# ccs811_v_1_0.net
KiCad netlist of a schematic drawn in EAGLE
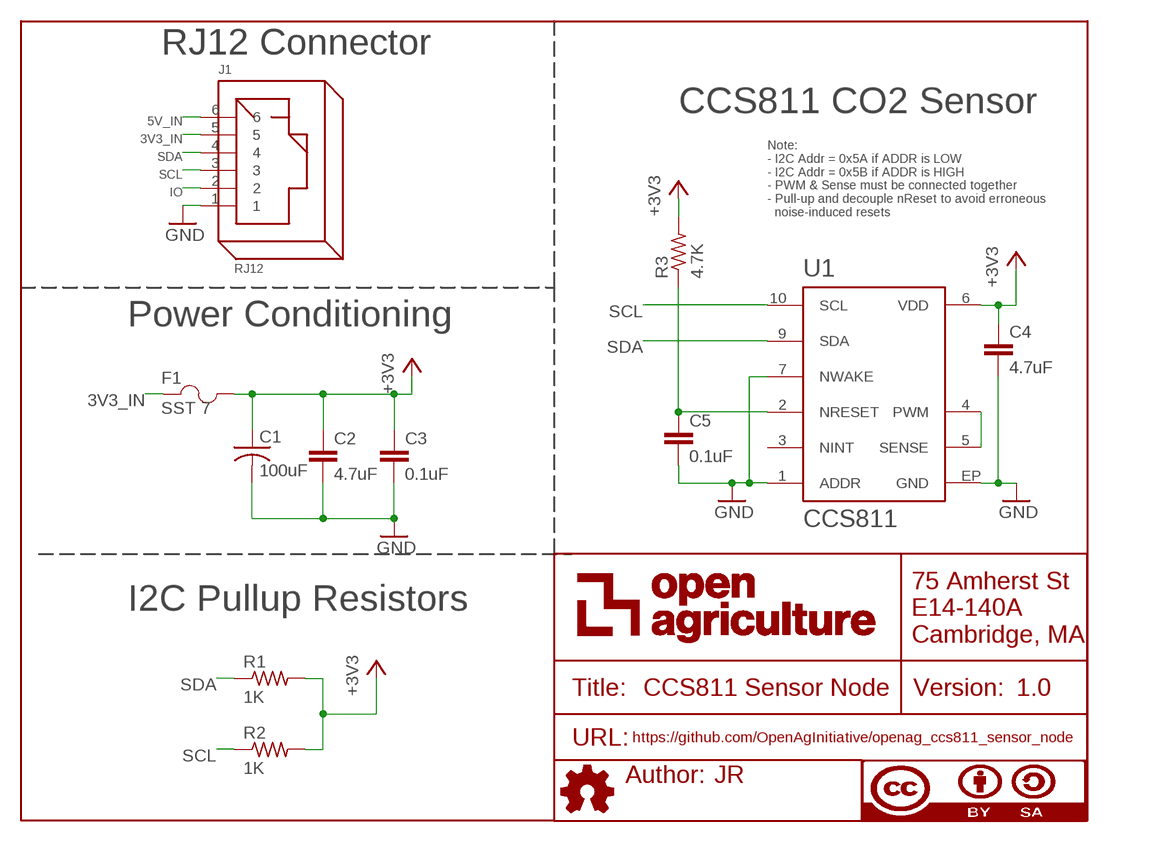
[diagram p0: schematic, sheet 1]

(export (version "E")
  (design (tool "Eeschema 10.0.6"))
  (components
    (comp (ref "C1")
      (value "100uF")
      (footprint "eagle-import:EEE-1HA101UP")
      (libsource (lib "eagle-import") (part "100UF-EEE-1HA101UP"))
    )
    (comp (ref "C2")
      (value "4.7uF")
      (footprint "eagle-import:C0805")
      (libsource (lib "eagle-import") (part "4.7UF-CL21A475KBQNNNE"))
    )
    (comp (ref "C3")
      (value "0.1uF")
      (footprint "eagle-import:C0603")
      (libsource (lib "eagle-import") (part "0.1UF-C0603C104K5RACTU"))
    )
    (comp (ref "C4")
      (value "4.7uF")
      (footprint "eagle-import:C0805")
      (libsource (lib "eagle-import") (part "4.7UF-CL21A475KBQNNNE"))
    )
    (comp (ref "C5")
      (value "0.1uF")
      (footprint "eagle-import:C0603")
      (libsource (lib "eagle-import") (part "0.1UF-C0603C104K5RACTU"))
    )
    (comp (ref "F1")
      (value "SST 7")
      (footprint "eagle-import:SS")
      (libsource (lib "eagle-import") (part "SST_7"))
    )
    (comp (ref "FRAME1")
      (value "DOCFIELD")
      (footprint "eagle-import:DOCFIELD")
      (description "CCS811 CO2 Sensor Node")
      (fields
        (field (name "AUTHOR") "JR")
        (field (name "TITLE") "CCS811 Sensor Node")
        (field (name "URL") "https://github.com/OpenAgInitiative/openag_ccs811_sensor_node")
      )
      (libsource (lib "eagle-import") (part "DOCFIELD"))
    )
    (comp (ref "J1")
      (value "RJ12")
      (footprint "eagle-import:RJ12")
      (libsource (lib "eagle-import") (part "A-2004-1-4-LP-N-R"))
    )
    (comp (ref "R1")
      (value "1K")
      (footprint "eagle-import:RC0603N")
      (libsource (lib "eagle-import") (part "1K-ERJ-PB3D1001V"))
    )
    (comp (ref "R2")
      (value "1K")
      (footprint "eagle-import:RC0603N")
      (libsource (lib "eagle-import") (part "1K-ERJ-PB3D1001V"))
    )
    (comp (ref "R3")
      (value "4.7K")
      (footprint "eagle-import:R1206")
      (libsource (lib "eagle-import") (part "4.7K-RC1206JR-074K7L"))
    )
    (comp (ref "U1")
      (value "CCS811")
      (footprint "eagle-import:CCS811")
      (libsource (lib "eagle-import") (part "CCS811"))
    )
  )
  (nets
    (net (code "1") (name "+3V3") (class "Default")
      (node (ref "C1") (pin "+") (pinfunction "1(+)_+") (pintype "passive"))
      (node (ref "C2") (pin "1") (pinfunction "1_1") (pintype "passive"))
      (node (ref "C3") (pin "1") (pinfunction "1_1") (pintype "passive"))
      (node (ref "C4") (pin "1") (pinfunction "1_1") (pintype "passive"))
      (node (ref "F1") (pin "2") (pinfunction "2_2") (pintype "passive"))
      (node (ref "R1") (pin "2") (pinfunction "2_2") (pintype "passive"))
      (node (ref "R2") (pin "2") (pinfunction "2_2") (pintype "passive"))
      (node (ref "R3") (pin "2") (pinfunction "2_2") (pintype "passive"))
      (node (ref "U1") (pin "6") (pinfunction "VDD_6") (pintype "power_in"))
    )
    (net (code "2") (name "3V3_IN") (class "Default")
      (node (ref "F1") (pin "1") (pinfunction "1_1") (pintype "passive"))
      (node (ref "J1") (pin "5") (pinfunction "5_5") (pintype "bidirectional"))
    )
    (net (code "3") (name "5V_IN") (class "Default")
      (node (ref "J1") (pin "6") (pinfunction "6_6") (pintype "bidirectional"))
    )
    (net (code "4") (name "GND") (class "Default")
      (node (ref "C1") (pin "-") (pinfunction "2(-)_-") (pintype "passive"))
      (node (ref "C2") (pin "2") (pinfunction "2_2") (pintype "passive"))
      (node (ref "C3") (pin "2") (pinfunction "2_2") (pintype "passive"))
      (node (ref "C4") (pin "2") (pinfunction "2_2") (pintype "passive"))
      (node (ref "C5") (pin "2") (pinfunction "2_2") (pintype "passive"))
      (node (ref "J1") (pin "1") (pinfunction "1_1") (pintype "bidirectional"))
      (node (ref "U1") (pin "1") (pinfunction "ADDR_1") (pintype "bidirectional"))
      (node (ref "U1") (pin "7") (pinfunction "NWAKE_7") (pintype "bidirectional"))
      (node (ref "U1") (pin "EP") (pinfunction "GND_EP") (pintype "power_in"))
    )
    (net (code "5") (name "IO") (class "Default")
      (node (ref "J1") (pin "2") (pinfunction "2_2") (pintype "bidirectional"))
    )
    (net (code "6") (name "Net-(U1-NRESET)") (class "Default")
      (node (ref "C5") (pin "1") (pinfunction "1_1") (pintype "passive"))
      (node (ref "R3") (pin "1") (pinfunction "1_1") (pintype "passive"))
      (node (ref "U1") (pin "2") (pinfunction "NRESET_2") (pintype "bidirectional"))
    )
    (net (code "7") (name "Net-(U1-PWM)") (class "Default")
      (node (ref "U1") (pin "4") (pinfunction "PWM_4") (pintype "bidirectional"))
      (node (ref "U1") (pin "5") (pinfunction "SENSE_5") (pintype "bidirectional"))
    )
    (net (code "8") (name "SCL") (class "Default")
      (node (ref "J1") (pin "3") (pinfunction "3_3") (pintype "bidirectional"))
      (node (ref "R2") (pin "1") (pinfunction "1_1") (pintype "passive"))
      (node (ref "U1") (pin "10") (pinfunction "SCL_10") (pintype "bidirectional"))
    )
    (net (code "9") (name "SDA") (class "Default")
      (node (ref "J1") (pin "4") (pinfunction "4_4") (pintype "bidirectional"))
      (node (ref "R1") (pin "1") (pinfunction "1_1") (pintype "passive"))
      (node (ref "U1") (pin "9") (pinfunction "SDA_9") (pintype "bidirectional"))
    )
    (net (code "10") (name "unconnected-(U1-NINT-Pad3)") (class "Default")
      (node (ref "U1") (pin "3") (pinfunction "NINT_3") (pintype "bidirectional"))
    )
  )
)
